# nixie-driver.net
KiCad netlist of a schematic drawn in EAGLE
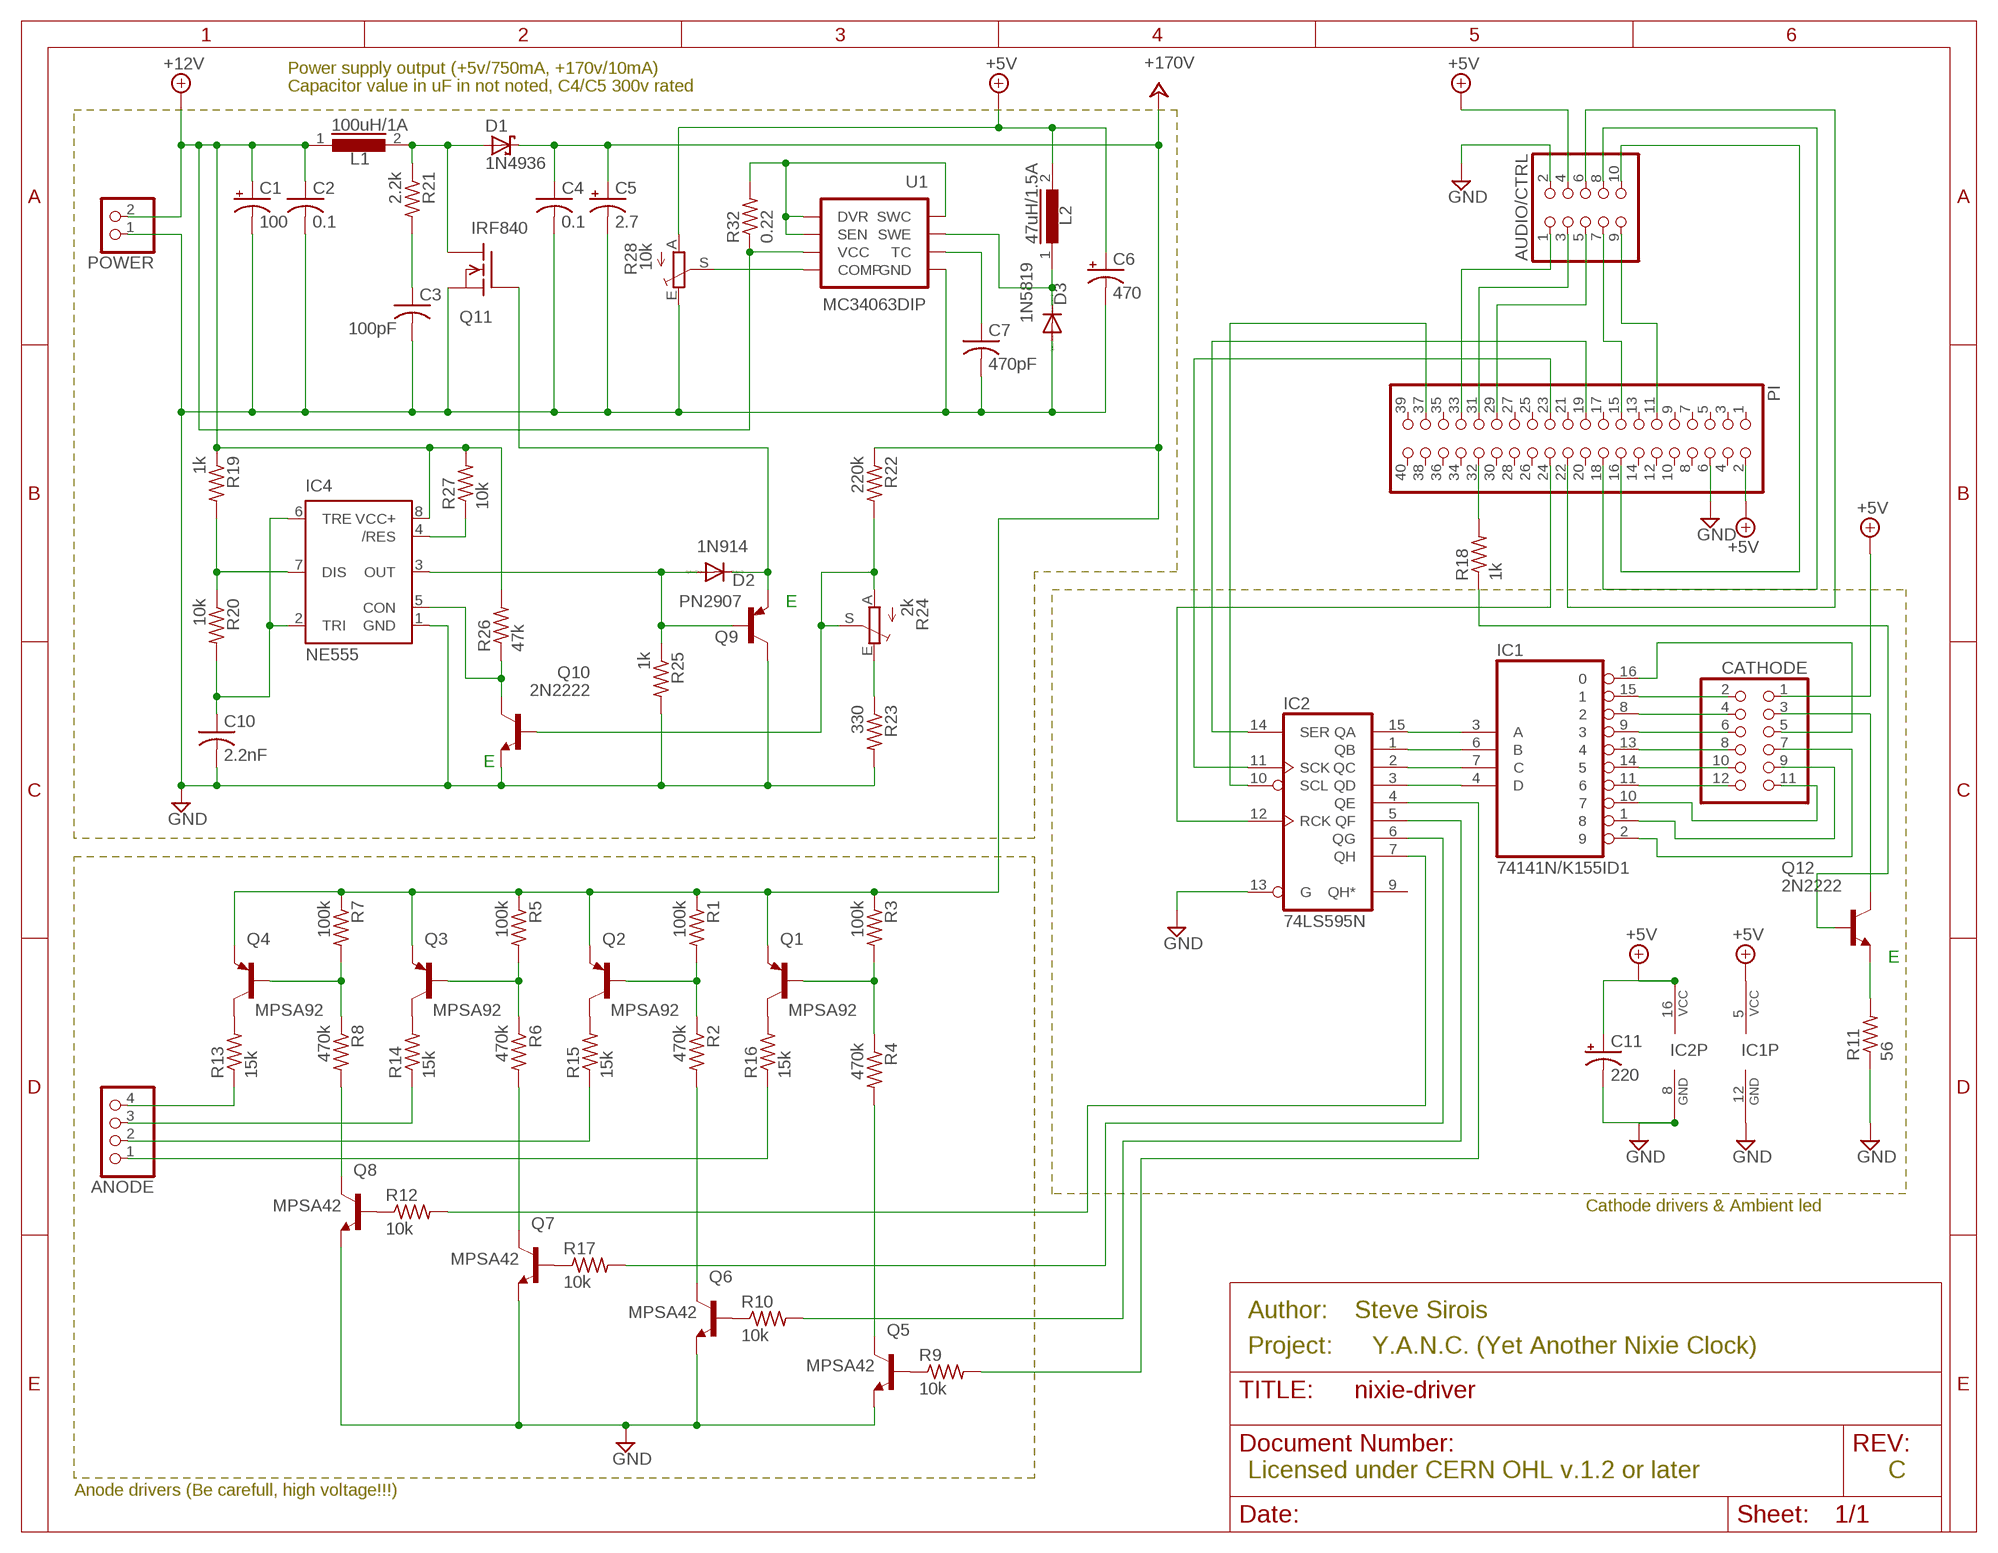
[diagram p0: schematic, sheet 1]

(export (version "E")
  (design (tool "Eeschema 10.0.6"))
  (components
    (comp (ref "ANODE")
      (value "PINHD-1X4")
      (footprint "eagle-import:1X04")
      (libsource (lib "eagle-import") (part "PINHD-1X4"))
    )
    (comp (ref "AUDIO/CTRL")
      (value "PINHD-2X5")
      (footprint "eagle-import:2X05")
      (libsource (lib "eagle-import") (part "PINHD-2X5"))
    )
    (comp (ref "C1")
      (value "100")
      (footprint "eagle-import:E2,5-6E")
      (libsource (lib "eagle-import") (part "CPOL-USE2,5-6E"))
    )
    (comp (ref "C2")
      (value "0.1")
      (footprint "eagle-import:C050-024X044")
      (libsource (lib "eagle-import") (part "C-US050-024X044"))
    )
    (comp (ref "C3")
      (value "100pF")
      (footprint "eagle-import:C050-024X044")
      (libsource (lib "eagle-import") (part "C-US050-024X044"))
    )
    (comp (ref "C4")
      (value "0.1")
      (footprint "eagle-import:C150-054X183")
      (libsource (lib "eagle-import") (part "C-US150-054X183"))
    )
    (comp (ref "C5")
      (value "2.7")
      (footprint "eagle-import:E2,5-7")
      (libsource (lib "eagle-import") (part "CPOL-USE2.5-7"))
    )
    (comp (ref "C6")
      (value "470")
      (footprint "eagle-import:E3,5-8")
      (libsource (lib "eagle-import") (part "CPOL-USE3.5-8"))
    )
    (comp (ref "C7")
      (value "470pF")
      (footprint "eagle-import:C050-024X044")
      (libsource (lib "eagle-import") (part "C-US050-024X044"))
    )
    (comp (ref "C10")
      (value "2.2nF")
      (footprint "eagle-import:C025-025X050")
      (libsource (lib "eagle-import") (part "C-US025-025X050"))
    )
    (comp (ref "C11")
      (value "220")
      (footprint "eagle-import:E3,5-8")
      (libsource (lib "eagle-import") (part "CPOL-USE3.5-8"))
    )
    (comp (ref "CATHODE")
      (value "PINHD-2X6")
      (footprint "eagle-import:2X06")
      (libsource (lib "eagle-import") (part "PINHD-2X6"))
    )
    (comp (ref "D1")
      (value "1N4936")
      (footprint "eagle-import:DO41-7.6")
      (libsource (lib "eagle-import") (part "1N5817-B"))
    )
    (comp (ref "D2")
      (value "1N914")
      (footprint "eagle-import:DO41-10")
      (libsource (lib "eagle-import") (part "1N4004"))
    )
    (comp (ref "D3")
      (value "1N5819")
      (footprint "eagle-import:DO41-10")
      (libsource (lib "eagle-import") (part "1N4004"))
    )
    (comp (ref "IC1")
      (value "74141N/K155ID1")
      (footprint "eagle-import:DIL16")
      (libsource (lib "eagle-import") (part "74141N"))
    )
    (comp (ref "IC2")
      (value "74LS595N")
      (footprint "eagle-import:DIL16")
      (libsource (lib "eagle-import") (part "74595NLS"))
    )
    (comp (ref "IC4")
      (value "NE555")
      (footprint "eagle-import:DIL-08")
      (fields (field (name "MF") "Arrow Electronics") (field (name "MPN") "NE555N"))
      (libsource (lib "eagle-import") (part "NE555"))
    )
    (comp (ref "L1")
      (value "100uH/1A")
      (footprint "eagle-import:MMICC7")
      (libsource (lib "eagle-import") (part "MMICC7"))
    )
    (comp (ref "L2")
      (value "47uH/1.5A")
      (footprint "eagle-import:MMICC7")
      (libsource (lib "eagle-import") (part "MMICC7"))
    )
    (comp (ref "PI")
      (value "PINHD-2X20")
      (footprint "eagle-import:2X20")
      (libsource (lib "eagle-import") (part "PINHD-2X20"))
    )
    (comp (ref "POWER")
      (value "PINHD-1X2")
      (footprint "eagle-import:1X02")
      (libsource (lib "eagle-import") (part "PINHD-1X2"))
    )
    (comp (ref "Q1")
      (value "MPSA92")
      (footprint "eagle-import:TO92-EBC")
      (libsource (lib "eagle-import") (part "-PNP-TO92-EBCMPSA92"))
    )
    (comp (ref "Q2")
      (value "MPSA92")
      (footprint "eagle-import:TO92-EBC")
      (libsource (lib "eagle-import") (part "-PNP-TO92-EBCMPSA92"))
    )
    (comp (ref "Q3")
      (value "MPSA92")
      (footprint "eagle-import:TO92-EBC")
      (libsource (lib "eagle-import") (part "-PNP-TO92-EBCMPSA92"))
    )
    (comp (ref "Q4")
      (value "MPSA92")
      (footprint "eagle-import:TO92-EBC")
      (libsource (lib "eagle-import") (part "-PNP-TO92-EBCMPSA92"))
    )
    (comp (ref "Q5")
      (value "MPSA42")
      (footprint "eagle-import:TO92-EBC")
      (libsource (lib "eagle-import") (part "-NPN-TO92-EBC"))
    )
    (comp (ref "Q6")
      (value "MPSA42")
      (footprint "eagle-import:TO92-EBC")
      (libsource (lib "eagle-import") (part "-NPN-TO92-EBC"))
    )
    (comp (ref "Q7")
      (value "MPSA42")
      (footprint "eagle-import:TO92-EBC")
      (libsource (lib "eagle-import") (part "-NPN-TO92-EBC"))
    )
    (comp (ref "Q8")
      (value "MPSA42")
      (footprint "eagle-import:TO92-EBC")
      (libsource (lib "eagle-import") (part "-NPN-TO92-EBC"))
    )
    (comp (ref "Q9")
      (value "PN2907")
      (footprint "eagle-import:TO92-CBE")
      (libsource (lib "eagle-import") (part "2N4126"))
    )
    (comp (ref "Q10")
      (value "2N2222")
      (footprint "eagle-import:TO92-EBC")
      (libsource (lib "eagle-import") (part "-NPN-TO92-EBC2N2222"))
    )
    (comp (ref "Q11")
      (value "IRF840")
      (footprint "eagle-import:TO220")
      (libsource (lib "eagle-import") (part "IRF840"))
    )
    (comp (ref "Q12")
      (value "2N2222")
      (footprint "eagle-import:TO92-EBC")
      (libsource (lib "eagle-import") (part "-NPN-TO92-EBC2N2222"))
    )
    (comp (ref "R1")
      (value "100k")
      (footprint "eagle-import:0207_10")
      (libsource (lib "eagle-import") (part "R-US_0207/10"))
    )
    (comp (ref "R2")
      (value "470k")
      (footprint "eagle-import:0207_10")
      (libsource (lib "eagle-import") (part "R-US_0207/10"))
    )
    (comp (ref "R3")
      (value "100k")
      (footprint "eagle-import:0207_10")
      (libsource (lib "eagle-import") (part "R-US_0207/10"))
    )
    (comp (ref "R4")
      (value "470k")
      (footprint "eagle-import:0207_10")
      (libsource (lib "eagle-import") (part "R-US_0207/10"))
    )
    (comp (ref "R5")
      (value "100k")
      (footprint "eagle-import:0207_10")
      (libsource (lib "eagle-import") (part "R-US_0207/10"))
    )
    (comp (ref "R6")
      (value "470k")
      (footprint "eagle-import:0207_10")
      (libsource (lib "eagle-import") (part "R-US_0207/10"))
    )
    (comp (ref "R7")
      (value "100k")
      (footprint "eagle-import:0207_10")
      (libsource (lib "eagle-import") (part "R-US_0207/10"))
    )
    (comp (ref "R8")
      (value "470k")
      (footprint "eagle-import:0207_10")
      (libsource (lib "eagle-import") (part "R-US_0207/10"))
    )
    (comp (ref "R9")
      (value "10k")
      (footprint "eagle-import:0207_10")
      (libsource (lib "eagle-import") (part "R-US_0207/10"))
    )
    (comp (ref "R10")
      (value "10k")
      (footprint "eagle-import:0207_10")
      (libsource (lib "eagle-import") (part "R-US_0207/10"))
    )
    (comp (ref "R11")
      (value "56")
      (footprint "eagle-import:0207_10")
      (libsource (lib "eagle-import") (part "R-US_0207/10"))
    )
    (comp (ref "R12")
      (value "10k")
      (footprint "eagle-import:0207_10")
      (libsource (lib "eagle-import") (part "R-US_0207/10"))
    )
    (comp (ref "R13")
      (value "15k")
      (footprint "eagle-import:0207_10")
      (libsource (lib "eagle-import") (part "R-US_0207/10"))
    )
    (comp (ref "R14")
      (value "15k")
      (footprint "eagle-import:0207_10")
      (libsource (lib "eagle-import") (part "R-US_0207/10"))
    )
    (comp (ref "R15")
      (value "15k")
      (footprint "eagle-import:0207_10")
      (libsource (lib "eagle-import") (part "R-US_0207/10"))
    )
    (comp (ref "R16")
      (value "15k")
      (footprint "eagle-import:0207_10")
      (libsource (lib "eagle-import") (part "R-US_0207/10"))
    )
    (comp (ref "R17")
      (value "10k")
      (footprint "eagle-import:0207_10")
      (libsource (lib "eagle-import") (part "R-US_0207/10"))
    )
    (comp (ref "R18")
      (value "1k")
      (footprint "eagle-import:0207_10")
      (libsource (lib "eagle-import") (part "R-US_0207/10"))
    )
    (comp (ref "R19")
      (value "1k")
      (footprint "eagle-import:0207_10")
      (libsource (lib "eagle-import") (part "R-US_0207/10"))
    )
    (comp (ref "R20")
      (value "10k")
      (footprint "eagle-import:0207_10")
      (libsource (lib "eagle-import") (part "R-US_0207/10"))
    )
    (comp (ref "R21")
      (value "2.2k")
      (footprint "eagle-import:0207_10")
      (libsource (lib "eagle-import") (part "R-US_0207/10"))
    )
    (comp (ref "R22")
      (value "220k")
      (footprint "eagle-import:0207_10")
      (libsource (lib "eagle-import") (part "R-US_0207/10"))
    )
    (comp (ref "R23")
      (value "330")
      (footprint "eagle-import:0207_10")
      (libsource (lib "eagle-import") (part "R-US_0207/10"))
    )
    (comp (ref "R24")
      (value "2k")
      (footprint "eagle-import:CA6V")
      (libsource (lib "eagle-import") (part "TRIM_EU-CA6V"))
    )
    (comp (ref "R25")
      (value "1k")
      (footprint "eagle-import:0207_10")
      (libsource (lib "eagle-import") (part "R-US_0207/10"))
    )
    (comp (ref "R26")
      (value "47k")
      (footprint "eagle-import:0207_10")
      (libsource (lib "eagle-import") (part "R-US_0207/10"))
    )
    (comp (ref "R27")
      (value "10k")
      (footprint "eagle-import:0207_10")
      (libsource (lib "eagle-import") (part "R-US_0207/10"))
    )
    (comp (ref "R28")
      (value "10k")
      (footprint "eagle-import:CA6V")
      (libsource (lib "eagle-import") (part "TRIM_EU-CA6V"))
    )
    (comp (ref "R32")
      (value "0.22")
      (footprint "eagle-import:0204V")
      (libsource (lib "eagle-import") (part "R-US_0204/2V"))
    )
    (comp (ref "U1")
      (value "MC34063DIP")
      (footprint "eagle-import:DIP-08")
      (libsource (lib "eagle-import") (part "MC34063DIP"))
    )
  )
  (nets
    (net (code "1") (name "+5V") (class "Default")
      (node (ref "AUDIO/CTRL") (pin "4") (pinfunction "4_4") (pintype "passive"))
      (node (ref "C11") (pin "+") (pinfunction "+_+") (pintype "passive"))
      (node (ref "C6") (pin "+") (pinfunction "+_+") (pintype "passive"))
      (node (ref "CATHODE") (pin "1") (pinfunction "1_1") (pintype "passive"))
      (node (ref "IC1") (pin "5") (pinfunction "VCC_5") (pintype "power_in"))
      (node (ref "IC2") (pin "16") (pinfunction "VCC_16") (pintype "power_in"))
      (node (ref "L2") (pin "2") (pinfunction "2_2") (pintype "passive"))
      (node (ref "PI") (pin "2") (pinfunction "2_2") (pintype "passive"))
      (node (ref "R28") (pin "A") (pinfunction "A_A") (pintype "passive"))
    )
    (net (code "2") (name "+12V") (class "Default")
      (node (ref "C1") (pin "+") (pinfunction "+_+") (pintype "passive"))
      (node (ref "C2") (pin "1") (pinfunction "1_1") (pintype "passive"))
      (node (ref "IC4") (pin "8") (pinfunction "VCC+_8") (pintype "power_in"))
      (node (ref "L1") (pin "1") (pinfunction "1_1") (pintype "passive"))
      (node (ref "POWER") (pin "2") (pinfunction "2_2") (pintype "passive"))
      (node (ref "R19") (pin "1") (pinfunction "1_1") (pintype "passive"))
      (node (ref "R26") (pin "2") (pinfunction "2_2") (pintype "passive"))
      (node (ref "R27") (pin "2") (pinfunction "2_2") (pintype "passive"))
      (node (ref "R32") (pin "1") (pinfunction "1_1") (pintype "passive"))
      (node (ref "U1") (pin "6") (pinfunction "VCC_6") (pintype "bidirectional"))
    )
    (net (code "3") (name "+170V") (class "Default")
      (node (ref "C4") (pin "1") (pinfunction "1_1") (pintype "passive"))
      (node (ref "C5") (pin "+") (pinfunction "+_+") (pintype "passive"))
      (node (ref "D1") (pin "C") (pinfunction "C_C") (pintype "passive"))
      (node (ref "Q1") (pin "E") (pinfunction "E_E") (pintype "passive"))
      (node (ref "Q2") (pin "E") (pinfunction "E_E") (pintype "passive"))
      (node (ref "Q3") (pin "E") (pinfunction "E_E") (pintype "passive"))
      (node (ref "Q4") (pin "E") (pinfunction "E_E") (pintype "passive"))
      (node (ref "R1") (pin "1") (pinfunction "1_1") (pintype "passive"))
      (node (ref "R22") (pin "1") (pinfunction "1_1") (pintype "passive"))
      (node (ref "R3") (pin "1") (pinfunction "1_1") (pintype "passive"))
      (node (ref "R5") (pin "1") (pinfunction "1_1") (pintype "passive"))
      (node (ref "R7") (pin "1") (pinfunction "1_1") (pintype "passive"))
    )
    (net (code "4") (name "GND") (class "Default")
      (node (ref "AUDIO/CTRL") (pin "2") (pinfunction "2_2") (pintype "passive"))
      (node (ref "C1") (pin "-") (pinfunction "-_-") (pintype "passive"))
      (node (ref "C10") (pin "2") (pinfunction "2_2") (pintype "passive"))
      (node (ref "C11") (pin "-") (pinfunction "-_-") (pintype "passive"))
      (node (ref "C2") (pin "2") (pinfunction "2_2") (pintype "passive"))
      (node (ref "C3") (pin "2") (pinfunction "2_2") (pintype "passive"))
      (node (ref "C4") (pin "2") (pinfunction "2_2") (pintype "passive"))
      (node (ref "C5") (pin "-") (pinfunction "-_-") (pintype "passive"))
      (node (ref "C6") (pin "-") (pinfunction "-_-") (pintype "passive"))
      (node (ref "C7") (pin "2") (pinfunction "2_2") (pintype "passive"))
      (node (ref "D3") (pin "A") (pinfunction "A_A") (pintype "passive"))
      (node (ref "IC1") (pin "12") (pinfunction "GND_12") (pintype "power_in"))
      (node (ref "IC2") (pin "13") (pinfunction "G_13") (pintype "input"))
      (node (ref "IC2") (pin "8") (pinfunction "GND_8") (pintype "power_in"))
      (node (ref "IC4") (pin "1") (pinfunction "GND_1") (pintype "power_in"))
      (node (ref "PI") (pin "6") (pinfunction "6_6") (pintype "passive"))
      (node (ref "POWER") (pin "1") (pinfunction "1_1") (pintype "passive"))
      (node (ref "Q10") (pin "E") (pinfunction "E_E") (pintype "passive"))
      (node (ref "Q11") (pin "3") (pinfunction "S_3") (pintype "passive"))
      (node (ref "Q5") (pin "E") (pinfunction "E_E") (pintype "passive"))
      (node (ref "Q6") (pin "E") (pinfunction "E_E") (pintype "passive"))
      (node (ref "Q7") (pin "E") (pinfunction "E_E") (pintype "passive"))
      (node (ref "Q8") (pin "E") (pinfunction "E_E") (pintype "passive"))
      (node (ref "Q9") (pin "C") (pinfunction "C_C") (pintype "passive"))
      (node (ref "R11") (pin "1") (pinfunction "1_1") (pintype "passive"))
      (node (ref "R23") (pin "2") (pinfunction "2_2") (pintype "passive"))
      (node (ref "R25") (pin "2") (pinfunction "2_2") (pintype "passive"))
      (node (ref "R28") (pin "E") (pinfunction "E_E") (pintype "passive"))
      (node (ref "U1") (pin "4") (pinfunction "GND_4") (pintype "bidirectional"))
    )
    (net (code "5") (name "Net-(ANODE-Pad1)") (class "Default")
      (node (ref "ANODE") (pin "1") (pinfunction "1_1") (pintype "passive"))
      (node (ref "R16") (pin "1") (pinfunction "1_1") (pintype "passive"))
    )
    (net (code "6") (name "Net-(ANODE-Pad2)") (class "Default")
      (node (ref "ANODE") (pin "2") (pinfunction "2_2") (pintype "passive"))
      (node (ref "R15") (pin "1") (pinfunction "1_1") (pintype "passive"))
    )
    (net (code "7") (name "Net-(ANODE-Pad3)") (class "Default")
      (node (ref "ANODE") (pin "3") (pinfunction "3_3") (pintype "passive"))
      (node (ref "R14") (pin "1") (pinfunction "1_1") (pintype "passive"))
    )
    (net (code "8") (name "Net-(ANODE-Pad4)") (class "Default")
      (node (ref "ANODE") (pin "4") (pinfunction "4_4") (pintype "passive"))
      (node (ref "R13") (pin "1") (pinfunction "1_1") (pintype "passive"))
    )
    (net (code "9") (name "Net-(AUDIO/CTRL-Pad1)") (class "Default")
      (node (ref "AUDIO/CTRL") (pin "1") (pinfunction "1_1") (pintype "passive"))
      (node (ref "PI") (pin "33") (pinfunction "33_33") (pintype "passive"))
    )
    (net (code "10") (name "Net-(AUDIO/CTRL-Pad3)") (class "Default")
      (node (ref "AUDIO/CTRL") (pin "3") (pinfunction "3_3") (pintype "passive"))
      (node (ref "PI") (pin "31") (pinfunction "31_31") (pintype "passive"))
    )
    (net (code "11") (name "Net-(AUDIO/CTRL-Pad5)") (class "Default")
      (node (ref "AUDIO/CTRL") (pin "5") (pinfunction "5_5") (pintype "passive"))
      (node (ref "PI") (pin "29") (pinfunction "29_29") (pintype "passive"))
    )
    (net (code "12") (name "Net-(AUDIO/CTRL-Pad6)") (class "Default")
      (node (ref "AUDIO/CTRL") (pin "6") (pinfunction "6_6") (pintype "passive"))
      (node (ref "PI") (pin "22") (pinfunction "22_22") (pintype "passive"))
    )
    (net (code "13") (name "Net-(AUDIO/CTRL-Pad7)") (class "Default")
      (node (ref "AUDIO/CTRL") (pin "7") (pinfunction "7_7") (pintype "passive"))
      (node (ref "PI") (pin "15") (pinfunction "15_15") (pintype "passive"))
    )
    (net (code "14") (name "Net-(AUDIO/CTRL-Pad8)") (class "Default")
      (node (ref "AUDIO/CTRL") (pin "8") (pinfunction "8_8") (pintype "passive"))
      (node (ref "PI") (pin "18") (pinfunction "18_18") (pintype "passive"))
    )
    (net (code "15") (name "Net-(AUDIO/CTRL-Pad9)") (class "Default")
      (node (ref "AUDIO/CTRL") (pin "9") (pinfunction "9_9") (pintype "passive"))
      (node (ref "PI") (pin "11") (pinfunction "11_11") (pintype "passive"))
    )
    (net (code "16") (name "Net-(AUDIO/CTRL-Pad10)") (class "Default")
      (node (ref "AUDIO/CTRL") (pin "10") (pinfunction "10_10") (pintype "passive"))
      (node (ref "PI") (pin "16") (pinfunction "16_16") (pintype "passive"))
    )
    (net (code "17") (name "Net-(C3-Pad1)") (class "Default")
      (node (ref "C3") (pin "1") (pinfunction "1_1") (pintype "passive"))
      (node (ref "R21") (pin "2") (pinfunction "2_2") (pintype "passive"))
    )
    (net (code "18") (name "Net-(CATHODE-Pad3)") (class "Default")
      (node (ref "CATHODE") (pin "3") (pinfunction "3_3") (pintype "passive"))
      (node (ref "Q12") (pin "C") (pinfunction "C_C") (pintype "passive"))
    )
    (net (code "19") (name "Net-(IC1A-0)") (class "Default")
      (node (ref "CATHODE") (pin "5") (pinfunction "5_5") (pintype "passive"))
      (node (ref "IC1") (pin "16") (pinfunction "0_16") (pintype "open_collector"))
    )
    (net (code "20") (name "Net-(IC1A-1)") (class "Default")
      (node (ref "CATHODE") (pin "2") (pinfunction "2_2") (pintype "passive"))
      (node (ref "IC1") (pin "15") (pinfunction "1_15") (pintype "open_collector"))
    )
    (net (code "21") (name "Net-(IC1A-2)") (class "Default")
      (node (ref "CATHODE") (pin "4") (pinfunction "4_4") (pintype "passive"))
      (node (ref "IC1") (pin "8") (pinfunction "2_8") (pintype "open_collector"))
    )
    (net (code "22") (name "Net-(IC1A-3)") (class "Default")
      (node (ref "CATHODE") (pin "6") (pinfunction "6_6") (pintype "passive"))
      (node (ref "IC1") (pin "9") (pinfunction "3_9") (pintype "open_collector"))
    )
    (net (code "23") (name "Net-(IC1A-4)") (class "Default")
      (node (ref "CATHODE") (pin "8") (pinfunction "8_8") (pintype "passive"))
      (node (ref "IC1") (pin "13") (pinfunction "4_13") (pintype "open_collector"))
    )
    (net (code "24") (name "Net-(IC1A-5)") (class "Default")
      (node (ref "CATHODE") (pin "10") (pinfunction "10_10") (pintype "passive"))
      (node (ref "IC1") (pin "14") (pinfunction "5_14") (pintype "open_collector"))
    )
    (net (code "25") (name "Net-(IC1A-6)") (class "Default")
      (node (ref "CATHODE") (pin "12") (pinfunction "12_12") (pintype "passive"))
      (node (ref "IC1") (pin "11") (pinfunction "6_11") (pintype "open_collector"))
    )
    (net (code "26") (name "Net-(IC1A-7)") (class "Default")
      (node (ref "CATHODE") (pin "11") (pinfunction "11_11") (pintype "passive"))
      (node (ref "IC1") (pin "10") (pinfunction "7_10") (pintype "open_collector"))
    )
    (net (code "27") (name "Net-(IC1A-8)") (class "Default")
      (node (ref "CATHODE") (pin "9") (pinfunction "9_9") (pintype "passive"))
      (node (ref "IC1") (pin "1") (pinfunction "8_1") (pintype "open_collector"))
    )
    (net (code "28") (name "Net-(IC1A-9)") (class "Default")
      (node (ref "CATHODE") (pin "7") (pinfunction "7_7") (pintype "passive"))
      (node (ref "IC1") (pin "2") (pinfunction "9_2") (pintype "open_collector"))
    )
    (net (code "29") (name "Net-(IC1A-A)") (class "Default")
      (node (ref "IC1") (pin "3") (pinfunction "A_3") (pintype "input"))
      (node (ref "IC2") (pin "15") (pinfunction "QA_15") (pintype "tri_state"))
    )
    (net (code "30") (name "Net-(IC1A-B)") (class "Default")
      (node (ref "IC1") (pin "6") (pinfunction "B_6") (pintype "input"))
      (node (ref "IC2") (pin "1") (pinfunction "QB_1") (pintype "tri_state"))
    )
    (net (code "31") (name "Net-(IC1A-C)") (class "Default")
      (node (ref "IC1") (pin "7") (pinfunction "C_7") (pintype "input"))
      (node (ref "IC2") (pin "2") (pinfunction "QC_2") (pintype "tri_state"))
    )
    (net (code "32") (name "Net-(IC1A-D)") (class "Default")
      (node (ref "IC1") (pin "4") (pinfunction "D_4") (pintype "input"))
      (node (ref "IC2") (pin "3") (pinfunction "QD_3") (pintype "tri_state"))
    )
    (net (code "33") (name "Net-(IC2A-QE)") (class "Default")
      (node (ref "IC2") (pin "4") (pinfunction "QE_4") (pintype "tri_state"))
      (node (ref "R9") (pin "2") (pinfunction "2_2") (pintype "passive"))
    )
    (net (code "34") (name "Net-(IC2A-QF)") (class "Default")
      (node (ref "IC2") (pin "5") (pinfunction "QF_5") (pintype "tri_state"))
      (node (ref "R10") (pin "2") (pinfunction "2_2") (pintype "passive"))
    )
    (net (code "35") (name "Net-(IC2A-QG)") (class "Default")
      (node (ref "IC2") (pin "6") (pinfunction "QG_6") (pintype "tri_state"))
      (node (ref "R17") (pin "2") (pinfunction "2_2") (pintype "passive"))
    )
    (net (code "36") (name "Net-(IC2A-QH)") (class "Default")
      (node (ref "IC2") (pin "7") (pinfunction "QH_7") (pintype "tri_state"))
      (node (ref "R12") (pin "2") (pinfunction "2_2") (pintype "passive"))
    )
    (net (code "37") (name "Net-(IC2A-RCK)") (class "Default")
      (node (ref "IC2") (pin "12") (pinfunction "RCK_12") (pintype "input"))
      (node (ref "PI") (pin "24") (pinfunction "24_24") (pintype "passive"))
    )
    (net (code "38") (name "Net-(IC2A-SCK)") (class "Default")
      (node (ref "IC2") (pin "11") (pinfunction "SCK_11") (pintype "input"))
      (node (ref "PI") (pin "23") (pinfunction "23_23") (pintype "passive"))
    )
    (net (code "39") (name "Net-(IC2A-SCL)") (class "Default")
      (node (ref "IC2") (pin "10") (pinfunction "SCL_10") (pintype "input"))
      (node (ref "PI") (pin "37") (pinfunction "37_37") (pintype "passive"))
    )
    (net (code "40") (name "Net-(IC2A-SER)") (class "Default")
      (node (ref "IC2") (pin "14") (pinfunction "SER_14") (pintype "input"))
      (node (ref "PI") (pin "19") (pinfunction "19_19") (pintype "passive"))
    )
    (net (code "41") (name "Net-(IC4-CON)") (class "Default")
      (node (ref "IC4") (pin "5") (pinfunction "CON_5") (pintype "input"))
      (node (ref "Q10") (pin "C") (pinfunction "C_C") (pintype "passive"))
      (node (ref "R26") (pin "1") (pinfunction "1_1") (pintype "passive"))
    )
    (net (code "42") (name "Net-(IC4-DIS)") (class "Default")
      (node (ref "IC4") (pin "7") (pinfunction "DIS_7") (pintype "input"))
      (node (ref "R19") (pin "2") (pinfunction "2_2") (pintype "passive"))
      (node (ref "R20") (pin "1") (pinfunction "1_1") (pintype "passive"))
    )
    (net (code "43") (name "Net-(IC4-OUT)") (class "Default")
      (node (ref "D2") (pin "A") (pinfunction "A_A") (pintype "passive"))
      (node (ref "IC4") (pin "3") (pinfunction "OUT_3") (pintype "output"))
      (node (ref "Q9") (pin "B") (pinfunction "B_B") (pintype "passive"))
      (node (ref "R25") (pin "1") (pinfunction "1_1") (pintype "passive"))
    )
    (net (code "44") (name "Net-(IC4-TRE)") (class "Default")
      (node (ref "C10") (pin "1") (pinfunction "1_1") (pintype "passive"))
      (node (ref "IC4") (pin "2") (pinfunction "TRI_2") (pintype "input"))
      (node (ref "IC4") (pin "6") (pinfunction "TRE_6") (pintype "input"))
      (node (ref "R20") (pin "2") (pinfunction "2_2") (pintype "passive"))
    )
    (net (code "45") (name "Net-(IC4-{slash}RES)") (class "Default")
      (node (ref "IC4") (pin "4") (pinfunction "/RES_4") (pintype "input"))
      (node (ref "R27") (pin "1") (pinfunction "1_1") (pintype "passive"))
    )
    (net (code "46") (name "Net-(PI-Pad32)") (class "Default")
      (node (ref "PI") (pin "32") (pinfunction "32_32") (pintype "passive"))
      (node (ref "R18") (pin "2") (pinfunction "2_2") (pintype "passive"))
    )
    (net (code "47") (name "Net-(Q1-PadB)") (class "Default")
      (node (ref "Q1") (pin "B") (pinfunction "B_B") (pintype "passive"))
      (node (ref "R3") (pin "2") (pinfunction "2_2") (pintype "passive"))
      (node (ref "R4") (pin "1") (pinfunction "1_1") (pintype "passive"))
    )
    (net (code "48") (name "Net-(Q1-PadC)") (class "Default")
      (node (ref "Q1") (pin "C") (pinfunction "C_C") (pintype "passive"))
      (node (ref "R16") (pin "2") (pinfunction "2_2") (pintype "passive"))
    )
    (net (code "49") (name "Net-(Q2-PadB)") (class "Default")
      (node (ref "Q2") (pin "B") (pinfunction "B_B") (pintype "passive"))
      (node (ref "R1") (pin "2") (pinfunction "2_2") (pintype "passive"))
      (node (ref "R2") (pin "1") (pinfunction "1_1") (pintype "passive"))
    )
    (net (code "50") (name "Net-(Q2-PadC)") (class "Default")
      (node (ref "Q2") (pin "C") (pinfunction "C_C") (pintype "passive"))
      (node (ref "R15") (pin "2") (pinfunction "2_2") (pintype "passive"))
    )
    (net (code "51") (name "Net-(Q3-PadB)") (class "Default")
      (node (ref "Q3") (pin "B") (pinfunction "B_B") (pintype "passive"))
      (node (ref "R5") (pin "2") (pinfunction "2_2") (pintype "passive"))
      (node (ref "R6") (pin "1") (pinfunction "1_1") (pintype "passive"))
    )
    (net (code "52") (name "Net-(Q3-PadC)") (class "Default")
      (node (ref "Q3") (pin "C") (pinfunction "C_C") (pintype "passive"))
      (node (ref "R14") (pin "2") (pinfunction "2_2") (pintype "passive"))
    )
    (net (code "53") (name "Net-(Q4-PadB)") (class "Default")
      (node (ref "Q4") (pin "B") (pinfunction "B_B") (pintype "passive"))
      (node (ref "R7") (pin "2") (pinfunction "2_2") (pintype "passive"))
      (node (ref "R8") (pin "1") (pinfunction "1_1") (pintype "passive"))
    )
    (net (code "54") (name "Net-(Q4-PadC)") (class "Default")
      (node (ref "Q4") (pin "C") (pinfunction "C_C") (pintype "passive"))
      (node (ref "R13") (pin "2") (pinfunction "2_2") (pintype "passive"))
    )
    (net (code "55") (name "Net-(Q5-PadB)") (class "Default")
      (node (ref "Q5") (pin "B") (pinfunction "B_B") (pintype "passive"))
      (node (ref "R9") (pin "1") (pinfunction "1_1") (pintype "passive"))
    )
    (net (code "56") (name "Net-(Q5-PadC)") (class "Default")
      (node (ref "Q5") (pin "C") (pinfunction "C_C") (pintype "passive"))
      (node (ref "R4") (pin "2") (pinfunction "2_2") (pintype "passive"))
    )
    (net (code "57") (name "Net-(Q6-PadB)") (class "Default")
      (node (ref "Q6") (pin "B") (pinfunction "B_B") (pintype "passive"))
      (node (ref "R10") (pin "1") (pinfunction "1_1") (pintype "passive"))
    )
    (net (code "58") (name "Net-(Q6-PadC)") (class "Default")
      (node (ref "Q6") (pin "C") (pinfunction "C_C") (pintype "passive"))
      (node (ref "R2") (pin "2") (pinfunction "2_2") (pintype "passive"))
    )
    (net (code "59") (name "Net-(Q7-PadB)") (class "Default")
      (node (ref "Q7") (pin "B") (pinfunction "B_B") (pintype "passive"))
      (node (ref "R17") (pin "1") (pinfunction "1_1") (pintype "passive"))
    )
    (net (code "60") (name "Net-(Q7-PadC)") (class "Default")
      (node (ref "Q7") (pin "C") (pinfunction "C_C") (pintype "passive"))
      (node (ref "R6") (pin "2") (pinfunction "2_2") (pintype "passive"))
    )
    (net (code "61") (name "Net-(Q8-PadB)") (class "Default")
      (node (ref "Q8") (pin "B") (pinfunction "B_B") (pintype "passive"))
      (node (ref "R12") (pin "1") (pinfunction "1_1") (pintype "passive"))
    )
    (net (code "62") (name "Net-(Q8-PadC)") (class "Default")
      (node (ref "Q8") (pin "C") (pinfunction "C_C") (pintype "passive"))
      (node (ref "R8") (pin "2") (pinfunction "2_2") (pintype "passive"))
    )
    (net (code "63") (name "Net-(Q10-PadB)") (class "Default")
      (node (ref "Q10") (pin "B") (pinfunction "B_B") (pintype "passive"))
      (node (ref "R22") (pin "2") (pinfunction "2_2") (pintype "passive"))
      (node (ref "R24") (pin "A") (pinfunction "A_A") (pintype "passive"))
      (node (ref "R24") (pin "S") (pinfunction "S_S") (pintype "passive"))
    )
    (net (code "64") (name "Net-(Q11-D)") (class "Default")
      (node (ref "D1") (pin "A") (pinfunction "A_A") (pintype "passive"))
      (node (ref "L1") (pin "2") (pinfunction "2_2") (pintype "passive"))
      (node (ref "Q11") (pin "2") (pinfunction "D_2") (pintype "passive"))
      (node (ref "R21") (pin "1") (pinfunction "1_1") (pintype "passive"))
    )
    (net (code "65") (name "Net-(Q11-G)") (class "Default")
      (node (ref "D2") (pin "C") (pinfunction "C_C") (pintype "passive"))
      (node (ref "Q11") (pin "1") (pinfunction "G_1") (pintype "passive"))
      (node (ref "Q9") (pin "E") (pinfunction "E_E") (pintype "passive"))
    )
    (net (code "66") (name "Net-(Q12-PadB)") (class "Default")
      (node (ref "Q12") (pin "B") (pinfunction "B_B") (pintype "passive"))
      (node (ref "R18") (pin "1") (pinfunction "1_1") (pintype "passive"))
    )
    (net (code "67") (name "Net-(Q12-PadE)") (class "Default")
      (node (ref "Q12") (pin "E") (pinfunction "E_E") (pintype "passive"))
      (node (ref "R11") (pin "2") (pinfunction "2_2") (pintype "passive"))
    )
    (net (code "68") (name "Net-(R23-Pad1)") (class "Default")
      (node (ref "R23") (pin "1") (pinfunction "1_1") (pintype "passive"))
      (node (ref "R24") (pin "E") (pinfunction "E_E") (pintype "passive"))
    )
    (net (code "69") (name "Net-(U1-COMP)") (class "Default")
      (node (ref "R28") (pin "S") (pinfunction "S_S") (pintype "passive"))
      (node (ref "U1") (pin "5") (pinfunction "COMP_5") (pintype "bidirectional"))
    )
    (net (code "70") (name "Net-(U1-DVR)") (class "Default")
      (node (ref "R32") (pin "2") (pinfunction "2_2") (pintype "passive"))
      (node (ref "U1") (pin "1") (pinfunction "SWC_1") (pintype "bidirectional"))
      (node (ref "U1") (pin "7") (pinfunction "SEN_7") (pintype "bidirectional"))
      (node (ref "U1") (pin "8") (pinfunction "DVR_8") (pintype "bidirectional"))
    )
    (net (code "71") (name "Net-(U1-SWE)") (class "Default")
      (node (ref "D3") (pin "C") (pinfunction "C_C") (pintype "passive"))
      (node (ref "L2") (pin "1") (pinfunction "1_1") (pintype "passive"))
      (node (ref "U1") (pin "2") (pinfunction "SWE_2") (pintype "bidirectional"))
    )
    (net (code "72") (name "Net-(U1-TC)") (class "Default")
      (node (ref "C7") (pin "1") (pinfunction "1_1") (pintype "passive"))
      (node (ref "U1") (pin "3") (pinfunction "TC_3") (pintype "bidirectional"))
    )
    (net (code "73") (name "unconnected-(IC2A-QH*-Pad9)") (class "Default")
      (node (ref "IC2") (pin "9") (pinfunction "QH*_9") (pintype "tri_state"))
    )
    (net (code "74") (name "unconnected-(PI-Pad1)") (class "Default")
      (node (ref "PI") (pin "1") (pinfunction "1_1") (pintype "passive"))
    )
    (net (code "75") (name "unconnected-(PI-Pad3)") (class "Default")
      (node (ref "PI") (pin "3") (pinfunction "3_3") (pintype "passive"))
    )
    (net (code "76") (name "unconnected-(PI-Pad4)") (class "Default")
      (node (ref "PI") (pin "4") (pinfunction "4_4") (pintype "passive"))
    )
    (net (code "77") (name "unconnected-(PI-Pad5)") (class "Default")
      (node (ref "PI") (pin "5") (pinfunction "5_5") (pintype "passive"))
    )
    (net (code "78") (name "unconnected-(PI-Pad7)") (class "Default")
      (node (ref "PI") (pin "7") (pinfunction "7_7") (pintype "passive"))
    )
    (net (code "79") (name "unconnected-(PI-Pad8)") (class "Default")
      (node (ref "PI") (pin "8") (pinfunction "8_8") (pintype "passive"))
    )
    (net (code "80") (name "unconnected-(PI-Pad9)") (class "Default")
      (node (ref "PI") (pin "9") (pinfunction "9_9") (pintype "passive"))
    )
    (net (code "81") (name "unconnected-(PI-Pad10)") (class "Default")
      (node (ref "PI") (pin "10") (pinfunction "10_10") (pintype "passive"))
    )
    (net (code "82") (name "unconnected-(PI-Pad12)") (class "Default")
      (node (ref "PI") (pin "12") (pinfunction "12_12") (pintype "passive"))
    )
    (net (code "83") (name "unconnected-(PI-Pad13)") (class "Default")
      (node (ref "PI") (pin "13") (pinfunction "13_13") (pintype "passive"))
    )
    (net (code "84") (name "unconnected-(PI-Pad14)") (class "Default")
      (node (ref "PI") (pin "14") (pinfunction "14_14") (pintype "passive"))
    )
    (net (code "85") (name "unconnected-(PI-Pad17)") (class "Default")
      (node (ref "PI") (pin "17") (pinfunction "17_17") (pintype "passive"))
    )
    (net (code "86") (name "unconnected-(PI-Pad20)") (class "Default")
      (node (ref "PI") (pin "20") (pinfunction "20_20") (pintype "passive"))
    )
    (net (code "87") (name "unconnected-(PI-Pad21)") (class "Default")
      (node (ref "PI") (pin "21") (pinfunction "21_21") (pintype "passive"))
    )
    (net (code "88") (name "unconnected-(PI-Pad25)") (class "Default")
      (node (ref "PI") (pin "25") (pinfunction "25_25") (pintype "passive"))
    )
    (net (code "89") (name "unconnected-(PI-Pad26)") (class "Default")
      (node (ref "PI") (pin "26") (pinfunction "26_26") (pintype "passive"))
    )
    (net (code "90") (name "unconnected-(PI-Pad27)") (class "Default")
      (node (ref "PI") (pin "27") (pinfunction "27_27") (pintype "passive"))
    )
    (net (code "91") (name "unconnected-(PI-Pad28)") (class "Default")
      (node (ref "PI") (pin "28") (pinfunction "28_28") (pintype "passive"))
    )
    (net (code "92") (name "unconnected-(PI-Pad30)") (class "Default")
      (node (ref "PI") (pin "30") (pinfunction "30_30") (pintype "passive"))
    )
    (net (code "93") (name "unconnected-(PI-Pad34)") (class "Default")
      (node (ref "PI") (pin "34") (pinfunction "34_34") (pintype "passive"))
    )
    (net (code "94") (name "unconnected-(PI-Pad35)") (class "Default")
      (node (ref "PI") (pin "35") (pinfunction "35_35") (pintype "passive"))
    )
    (net (code "95") (name "unconnected-(PI-Pad36)") (class "Default")
      (node (ref "PI") (pin "36") (pinfunction "36_36") (pintype "passive"))
    )
    (net (code "96") (name "unconnected-(PI-Pad38)") (class "Default")
      (node (ref "PI") (pin "38") (pinfunction "38_38") (pintype "passive"))
    )
    (net (code "97") (name "unconnected-(PI-Pad39)") (class "Default")
      (node (ref "PI") (pin "39") (pinfunction "39_39") (pintype "passive"))
    )
    (net (code "98") (name "unconnected-(PI-Pad40)") (class "Default")
      (node (ref "PI") (pin "40") (pinfunction "40_40") (pintype "passive"))
    )
  )
)
